# ESP_1.net
KiCad netlist of a schematic drawn in Altium Designer
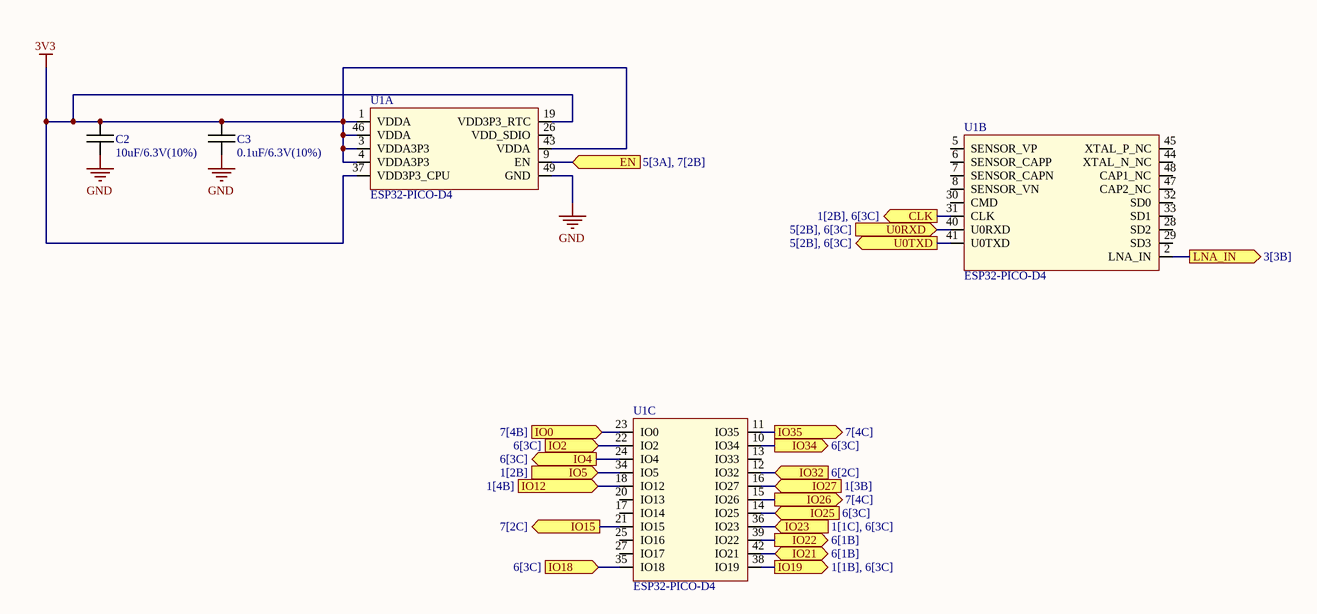
[diagram p0: ESP (1).SchDoc]

(export (version "E")
  (design (tool "Eeschema 10.0.6"))
  (components
    (comp (ref "C2")
      (value "10uF/6.3V(10%)")
      (footprint "CAPC1005X06N")
      (libsource (lib "SCHLibrary") (part "Capacitor"))
    )
    (comp (ref "C3")
      (value "0.1uF/6.3V(10%)")
      (footprint "CAPC1005X06N")
      (libsource (lib "SCHLibrary") (part "Capacitor"))
    )
    (comp (ref "U1")
      (value "ESP32-PICO-D4")
      (footprint "PQFN50P700X700X104_HS-49N")
      (libsource (lib "SCHLibrary") (part "ESP32"))
    )
  )
  (nets
    (net (code "1") (name "/CLK") (class "Default")
      (node (ref "U1") (pin "31") (pinfunction "CLK_31") (pintype "passive"))
    )
    (net (code "2") (name "/EN") (class "Default")
      (node (ref "U1") (pin "9") (pinfunction "EN_9") (pintype "passive"))
    )
    (net (code "3") (name "/IO0") (class "Default")
      (node (ref "U1") (pin "23") (pinfunction "IO0_23") (pintype "passive"))
    )
    (net (code "4") (name "/IO2") (class "Default")
      (node (ref "U1") (pin "22") (pinfunction "IO2_22") (pintype "passive"))
    )
    (net (code "5") (name "/IO4") (class "Default")
      (node (ref "U1") (pin "24") (pinfunction "IO4_24") (pintype "passive"))
    )
    (net (code "6") (name "/IO5") (class "Default")
      (node (ref "U1") (pin "34") (pinfunction "IO5_34") (pintype "passive"))
    )
    (net (code "7") (name "/IO12") (class "Default")
      (node (ref "U1") (pin "18") (pinfunction "IO12_18") (pintype "passive"))
    )
    (net (code "8") (name "/IO15") (class "Default")
      (node (ref "U1") (pin "21") (pinfunction "IO15_21") (pintype "passive"))
    )
    (net (code "9") (name "/IO18") (class "Default")
      (node (ref "U1") (pin "35") (pinfunction "IO18_35") (pintype "passive"))
    )
    (net (code "10") (name "/IO19") (class "Default")
      (node (ref "U1") (pin "38") (pinfunction "IO19_38") (pintype "passive"))
    )
    (net (code "11") (name "/IO21") (class "Default")
      (node (ref "U1") (pin "42") (pinfunction "IO21_42") (pintype "passive"))
    )
    (net (code "12") (name "/IO22") (class "Default")
      (node (ref "U1") (pin "39") (pinfunction "IO22_39") (pintype "passive"))
    )
    (net (code "13") (name "/IO23") (class "Default")
      (node (ref "U1") (pin "36") (pinfunction "IO23_36") (pintype "passive"))
    )
    (net (code "14") (name "/IO25") (class "Default")
      (node (ref "U1") (pin "14") (pinfunction "IO25_14") (pintype "passive"))
    )
    (net (code "15") (name "/IO26") (class "Default")
      (node (ref "U1") (pin "15") (pinfunction "IO26_15") (pintype "passive"))
    )
    (net (code "16") (name "/IO27") (class "Default")
      (node (ref "U1") (pin "16") (pinfunction "IO27_16") (pintype "passive"))
    )
    (net (code "17") (name "/IO32") (class "Default")
      (node (ref "U1") (pin "12") (pinfunction "IO32_12") (pintype "passive"))
    )
    (net (code "18") (name "/IO34") (class "Default")
      (node (ref "U1") (pin "10") (pinfunction "IO34_10") (pintype "passive"))
    )
    (net (code "19") (name "/IO35") (class "Default")
      (node (ref "U1") (pin "11") (pinfunction "IO35_11") (pintype "passive"))
    )
    (net (code "20") (name "/LNA_IN") (class "Default")
      (node (ref "U1") (pin "2") (pinfunction "LNA_IN_2") (pintype "passive"))
    )
    (net (code "21") (name "/U0RXD") (class "Default")
      (node (ref "U1") (pin "40") (pinfunction "U0RXD_40") (pintype "passive"))
    )
    (net (code "22") (name "/U0TXD") (class "Default")
      (node (ref "U1") (pin "41") (pinfunction "U0TXD_41") (pintype "passive"))
    )
    (net (code "23") (name "3V3") (class "Default")
      (node (ref "C2") (pin "2") (pinfunction "2_2") (pintype "passive"))
      (node (ref "C3") (pin "2") (pinfunction "2_2") (pintype "passive"))
      (node (ref "U1") (pin "1") (pinfunction "VDDA_1") (pintype "passive"))
      (node (ref "U1") (pin "19") (pinfunction "VDD3P3_RTC_19") (pintype "passive"))
      (node (ref "U1") (pin "3") (pinfunction "VDDA3P3_3") (pintype "passive"))
      (node (ref "U1") (pin "37") (pinfunction "VDD3P3_CPU_37") (pintype "passive"))
      (node (ref "U1") (pin "4") (pinfunction "VDDA3P3_4") (pintype "passive"))
      (node (ref "U1") (pin "43") (pinfunction "VDDA_43") (pintype "passive"))
      (node (ref "U1") (pin "46") (pinfunction "VDDA_46") (pintype "passive"))
    )
    (net (code "24") (name "GND") (class "Default")
      (node (ref "C2") (pin "1") (pinfunction "1_1") (pintype "passive"))
      (node (ref "C3") (pin "1") (pinfunction "1_1") (pintype "passive"))
      (node (ref "U1") (pin "49") (pinfunction "GND_49") (pintype "passive"))
    )
    (net (code "25") (name "unconnected-(U1A-VDD_SDIO-Pad26)") (class "Default")
      (node (ref "U1") (pin "26") (pinfunction "VDD_SDIO_26") (pintype "passive"))
    )
    (net (code "26") (name "unconnected-(U1B-CAP1_NC-Pad48)") (class "Default")
      (node (ref "U1") (pin "48") (pinfunction "CAP1_NC_48") (pintype "passive"))
    )
    (net (code "27") (name "unconnected-(U1B-CAP2_NC-Pad47)") (class "Default")
      (node (ref "U1") (pin "47") (pinfunction "CAP2_NC_47") (pintype "passive"))
    )
    (net (code "28") (name "unconnected-(U1B-CMD-Pad30)") (class "Default")
      (node (ref "U1") (pin "30") (pinfunction "CMD_30") (pintype "passive"))
    )
    (net (code "29") (name "unconnected-(U1B-SD0-Pad32)") (class "Default")
      (node (ref "U1") (pin "32") (pinfunction "SD0_32") (pintype "passive"))
    )
    (net (code "30") (name "unconnected-(U1B-SD1-Pad33)") (class "Default")
      (node (ref "U1") (pin "33") (pinfunction "SD1_33") (pintype "passive"))
    )
    (net (code "31") (name "unconnected-(U1B-SD2-Pad28)") (class "Default")
      (node (ref "U1") (pin "28") (pinfunction "SD2_28") (pintype "passive"))
    )
    (net (code "32") (name "unconnected-(U1B-SD3-Pad29)") (class "Default")
      (node (ref "U1") (pin "29") (pinfunction "SD3_29") (pintype "passive"))
    )
    (net (code "33") (name "unconnected-(U1B-SENSOR_CAPN-Pad7)") (class "Default")
      (node (ref "U1") (pin "7") (pinfunction "SENSOR_CAPN_7") (pintype "passive"))
    )
    (net (code "34") (name "unconnected-(U1B-SENSOR_CAPP-Pad6)") (class "Default")
      (node (ref "U1") (pin "6") (pinfunction "SENSOR_CAPP_6") (pintype "passive"))
    )
    (net (code "35") (name "unconnected-(U1B-SENSOR_VN-Pad8)") (class "Default")
      (node (ref "U1") (pin "8") (pinfunction "SENSOR_VN_8") (pintype "passive"))
    )
    (net (code "36") (name "unconnected-(U1B-SENSOR_VP-Pad5)") (class "Default")
      (node (ref "U1") (pin "5") (pinfunction "SENSOR_VP_5") (pintype "passive"))
    )
    (net (code "37") (name "unconnected-(U1B-XTAL_N_NC-Pad44)") (class "Default")
      (node (ref "U1") (pin "44") (pinfunction "XTAL_N_NC_44") (pintype "passive"))
    )
    (net (code "38") (name "unconnected-(U1B-XTAL_P_NC-Pad45)") (class "Default")
      (node (ref "U1") (pin "45") (pinfunction "XTAL_P_NC_45") (pintype "passive"))
    )
    (net (code "39") (name "unconnected-(U1C-IO13-Pad20)") (class "Default")
      (node (ref "U1") (pin "20") (pinfunction "IO13_20") (pintype "passive"))
    )
    (net (code "40") (name "unconnected-(U1C-IO14-Pad17)") (class "Default")
      (node (ref "U1") (pin "17") (pinfunction "IO14_17") (pintype "passive"))
    )
    (net (code "41") (name "unconnected-(U1C-IO16-Pad25)") (class "Default")
      (node (ref "U1") (pin "25") (pinfunction "IO16_25") (pintype "passive"))
    )
    (net (code "42") (name "unconnected-(U1C-IO17-Pad27)") (class "Default")
      (node (ref "U1") (pin "27") (pinfunction "IO17_27") (pintype "passive"))
    )
    (net (code "43") (name "unconnected-(U1C-IO33-Pad13)") (class "Default")
      (node (ref "U1") (pin "13") (pinfunction "IO33_13") (pintype "passive"))
    )
  )
)
